# logo.net
KiCad netlist of a schematic drawn in EAGLE
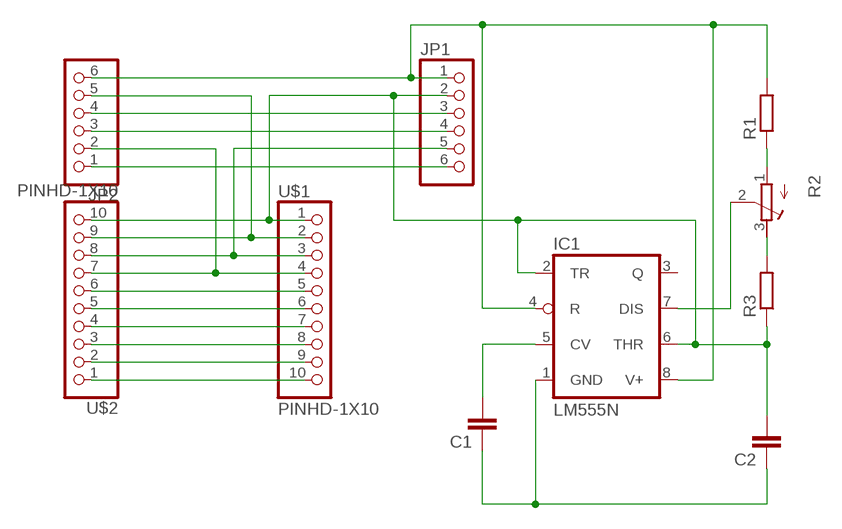
[diagram p0: schematic, sheet 1]

(export (version "E")
  (design (tool "Eeschema 10.0.6"))
  (components
    (comp (ref "C1")
      (value "C-EU050-025X075")
      (footprint "eagle-import:C050-025X075")
      (libsource (lib "eagle-import") (part "C-EU050-025X075"))
    )
    (comp (ref "C2")
      (value "C-EU050-025X075")
      (footprint "eagle-import:C050-025X075")
      (libsource (lib "eagle-import") (part "C-EU050-025X075"))
    )
    (comp (ref "IC1")
      (value "LM555N")
      (footprint "eagle-import:DIL08-ROUND")
      (libsource (lib "eagle-import") (part "555NLM"))
    )
    (comp (ref "JP1")
      (value "PINHD-1X6B")
      (footprint "eagle-import:1X06-BIG")
      (libsource (lib "eagle-import") (part "PINHD-1X6B"))
    )
    (comp (ref "JP2")
      (value "PINHD-1X6B")
      (footprint "eagle-import:1X06-BIG")
      (libsource (lib "eagle-import") (part "PINHD-1X6B"))
    )
    (comp (ref "R1")
      (value "R-EU_0204/7")
      (footprint "eagle-import:0204_7")
      (libsource (lib "eagle-import") (part "R-EU_0204/7"))
    )
    (comp (ref "R2")
      (value "R-TRIMM64W")
      (footprint "eagle-import:RTRIM64W")
      (libsource (lib "eagle-import") (part "R-TRIMM64W"))
    )
    (comp (ref "R3")
      (value "R-EU_0204/7")
      (footprint "eagle-import:0204_7")
      (libsource (lib "eagle-import") (part "R-EU_0204/7"))
    )
    (comp (ref "U$1")
      (value "PINHD-1X10")
      (footprint "eagle-import:1X10-BIG")
      (libsource (lib "eagle-import") (part "PINHD-1X10"))
    )
    (comp (ref "U$2")
      (value "PINHD-1X10")
      (footprint "eagle-import:1X10-BIG")
      (libsource (lib "eagle-import") (part "PINHD-1X10"))
    )
  )
  (nets
    (net (code "1") (name "Net-(IC1-CV)") (class "Default")
      (node (ref "C1") (pin "2") (pinfunction "2_2") (pintype "passive"))
      (node (ref "IC1") (pin "5") (pinfunction "CV_5") (pintype "input"))
    )
    (net (code "2") (name "Net-(IC1-DIS)") (class "Default")
      (node (ref "IC1") (pin "7") (pinfunction "DIS_7") (pintype "input"))
      (node (ref "R2") (pin "2") (pinfunction "S_2") (pintype "passive"))
    )
    (net (code "3") (name "Net-(IC1-GND)") (class "Default")
      (node (ref "C1") (pin "1") (pinfunction "1_1") (pintype "passive"))
      (node (ref "C2") (pin "1") (pinfunction "1_1") (pintype "passive"))
      (node (ref "IC1") (pin "1") (pinfunction "GND_1") (pintype "power_in"))
    )
    (net (code "4") (name "Net-(IC1-R)") (class "Default")
      (node (ref "IC1") (pin "4") (pinfunction "R_4") (pintype "input"))
      (node (ref "IC1") (pin "8") (pinfunction "V+_8") (pintype "power_in"))
      (node (ref "JP1") (pin "1") (pinfunction "1_1") (pintype "passive"))
      (node (ref "JP2") (pin "6") (pinfunction "6_6") (pintype "passive"))
      (node (ref "R1") (pin "2") (pinfunction "2_2") (pintype "passive"))
    )
    (net (code "5") (name "Net-(IC1-THR)") (class "Default")
      (node (ref "C2") (pin "2") (pinfunction "2_2") (pintype "passive"))
      (node (ref "IC1") (pin "2") (pinfunction "TR_2") (pintype "input"))
      (node (ref "IC1") (pin "6") (pinfunction "THR_6") (pintype "input"))
      (node (ref "JP1") (pin "2") (pinfunction "2_2") (pintype "passive"))
      (node (ref "R3") (pin "1") (pinfunction "1_1") (pintype "passive"))
      (node (ref "U$1") (pin "1") (pinfunction "1_1") (pintype "passive"))
      (node (ref "U$2") (pin "10") (pinfunction "10_10") (pintype "passive"))
    )
    (net (code "6") (name "Net-(JP1-Pad3)") (class "Default")
      (node (ref "JP1") (pin "3") (pinfunction "3_3") (pintype "passive"))
      (node (ref "JP2") (pin "4") (pinfunction "4_4") (pintype "passive"))
    )
    (net (code "7") (name "Net-(JP1-Pad4)") (class "Default")
      (node (ref "JP1") (pin "4") (pinfunction "4_4") (pintype "passive"))
      (node (ref "JP2") (pin "3") (pinfunction "3_3") (pintype "passive"))
    )
    (net (code "8") (name "Net-(JP1-Pad5)") (class "Default")
      (node (ref "JP1") (pin "5") (pinfunction "5_5") (pintype "passive"))
      (node (ref "U$1") (pin "3") (pinfunction "3_3") (pintype "passive"))
      (node (ref "U$2") (pin "8") (pinfunction "8_8") (pintype "passive"))
    )
    (net (code "9") (name "Net-(JP1-Pad6)") (class "Default")
      (node (ref "JP1") (pin "6") (pinfunction "6_6") (pintype "passive"))
      (node (ref "JP2") (pin "1") (pinfunction "1_1") (pintype "passive"))
    )
    (net (code "10") (name "Net-(JP2-Pad2)") (class "Default")
      (node (ref "JP2") (pin "2") (pinfunction "2_2") (pintype "passive"))
      (node (ref "U$1") (pin "4") (pinfunction "4_4") (pintype "passive"))
      (node (ref "U$2") (pin "7") (pinfunction "7_7") (pintype "passive"))
    )
    (net (code "11") (name "Net-(JP2-Pad5)") (class "Default")
      (node (ref "JP2") (pin "5") (pinfunction "5_5") (pintype "passive"))
      (node (ref "U$1") (pin "2") (pinfunction "2_2") (pintype "passive"))
      (node (ref "U$2") (pin "9") (pinfunction "9_9") (pintype "passive"))
    )
    (net (code "12") (name "Net-(R2-A)") (class "Default")
      (node (ref "R1") (pin "1") (pinfunction "1_1") (pintype "passive"))
      (node (ref "R2") (pin "1") (pinfunction "A_1") (pintype "passive"))
    )
    (net (code "13") (name "Net-(R2-E)") (class "Default")
      (node (ref "R2") (pin "3") (pinfunction "E_3") (pintype "passive"))
      (node (ref "R3") (pin "2") (pinfunction "2_2") (pintype "passive"))
    )
    (net (code "14") (name "Net-(U$1-Pad5)") (class "Default")
      (node (ref "U$1") (pin "5") (pinfunction "5_5") (pintype "passive"))
      (node (ref "U$2") (pin "6") (pinfunction "6_6") (pintype "passive"))
    )
    (net (code "15") (name "Net-(U$1-Pad6)") (class "Default")
      (node (ref "U$1") (pin "6") (pinfunction "6_6") (pintype "passive"))
      (node (ref "U$2") (pin "5") (pinfunction "5_5") (pintype "passive"))
    )
    (net (code "16") (name "Net-(U$1-Pad7)") (class "Default")
      (node (ref "U$1") (pin "7") (pinfunction "7_7") (pintype "passive"))
      (node (ref "U$2") (pin "4") (pinfunction "4_4") (pintype "passive"))
    )
    (net (code "17") (name "Net-(U$1-Pad8)") (class "Default")
      (node (ref "U$1") (pin "8") (pinfunction "8_8") (pintype "passive"))
      (node (ref "U$2") (pin "3") (pinfunction "3_3") (pintype "passive"))
    )
    (net (code "18") (name "Net-(U$1-Pad9)") (class "Default")
      (node (ref "U$1") (pin "9") (pinfunction "9_9") (pintype "passive"))
      (node (ref "U$2") (pin "2") (pinfunction "2_2") (pintype "passive"))
    )
    (net (code "19") (name "Net-(U$1-Pad10)") (class "Default")
      (node (ref "U$1") (pin "10") (pinfunction "10_10") (pintype "passive"))
      (node (ref "U$2") (pin "1") (pinfunction "1_1") (pintype "passive"))
    )
    (net (code "20") (name "unconnected-(IC1-Q-Pad3)") (class "Default")
      (node (ref "IC1") (pin "3") (pinfunction "Q_3") (pintype "output"))
    )
  )
)
